# inputs.net
KiCad netlist of a schematic drawn in Altium Designer
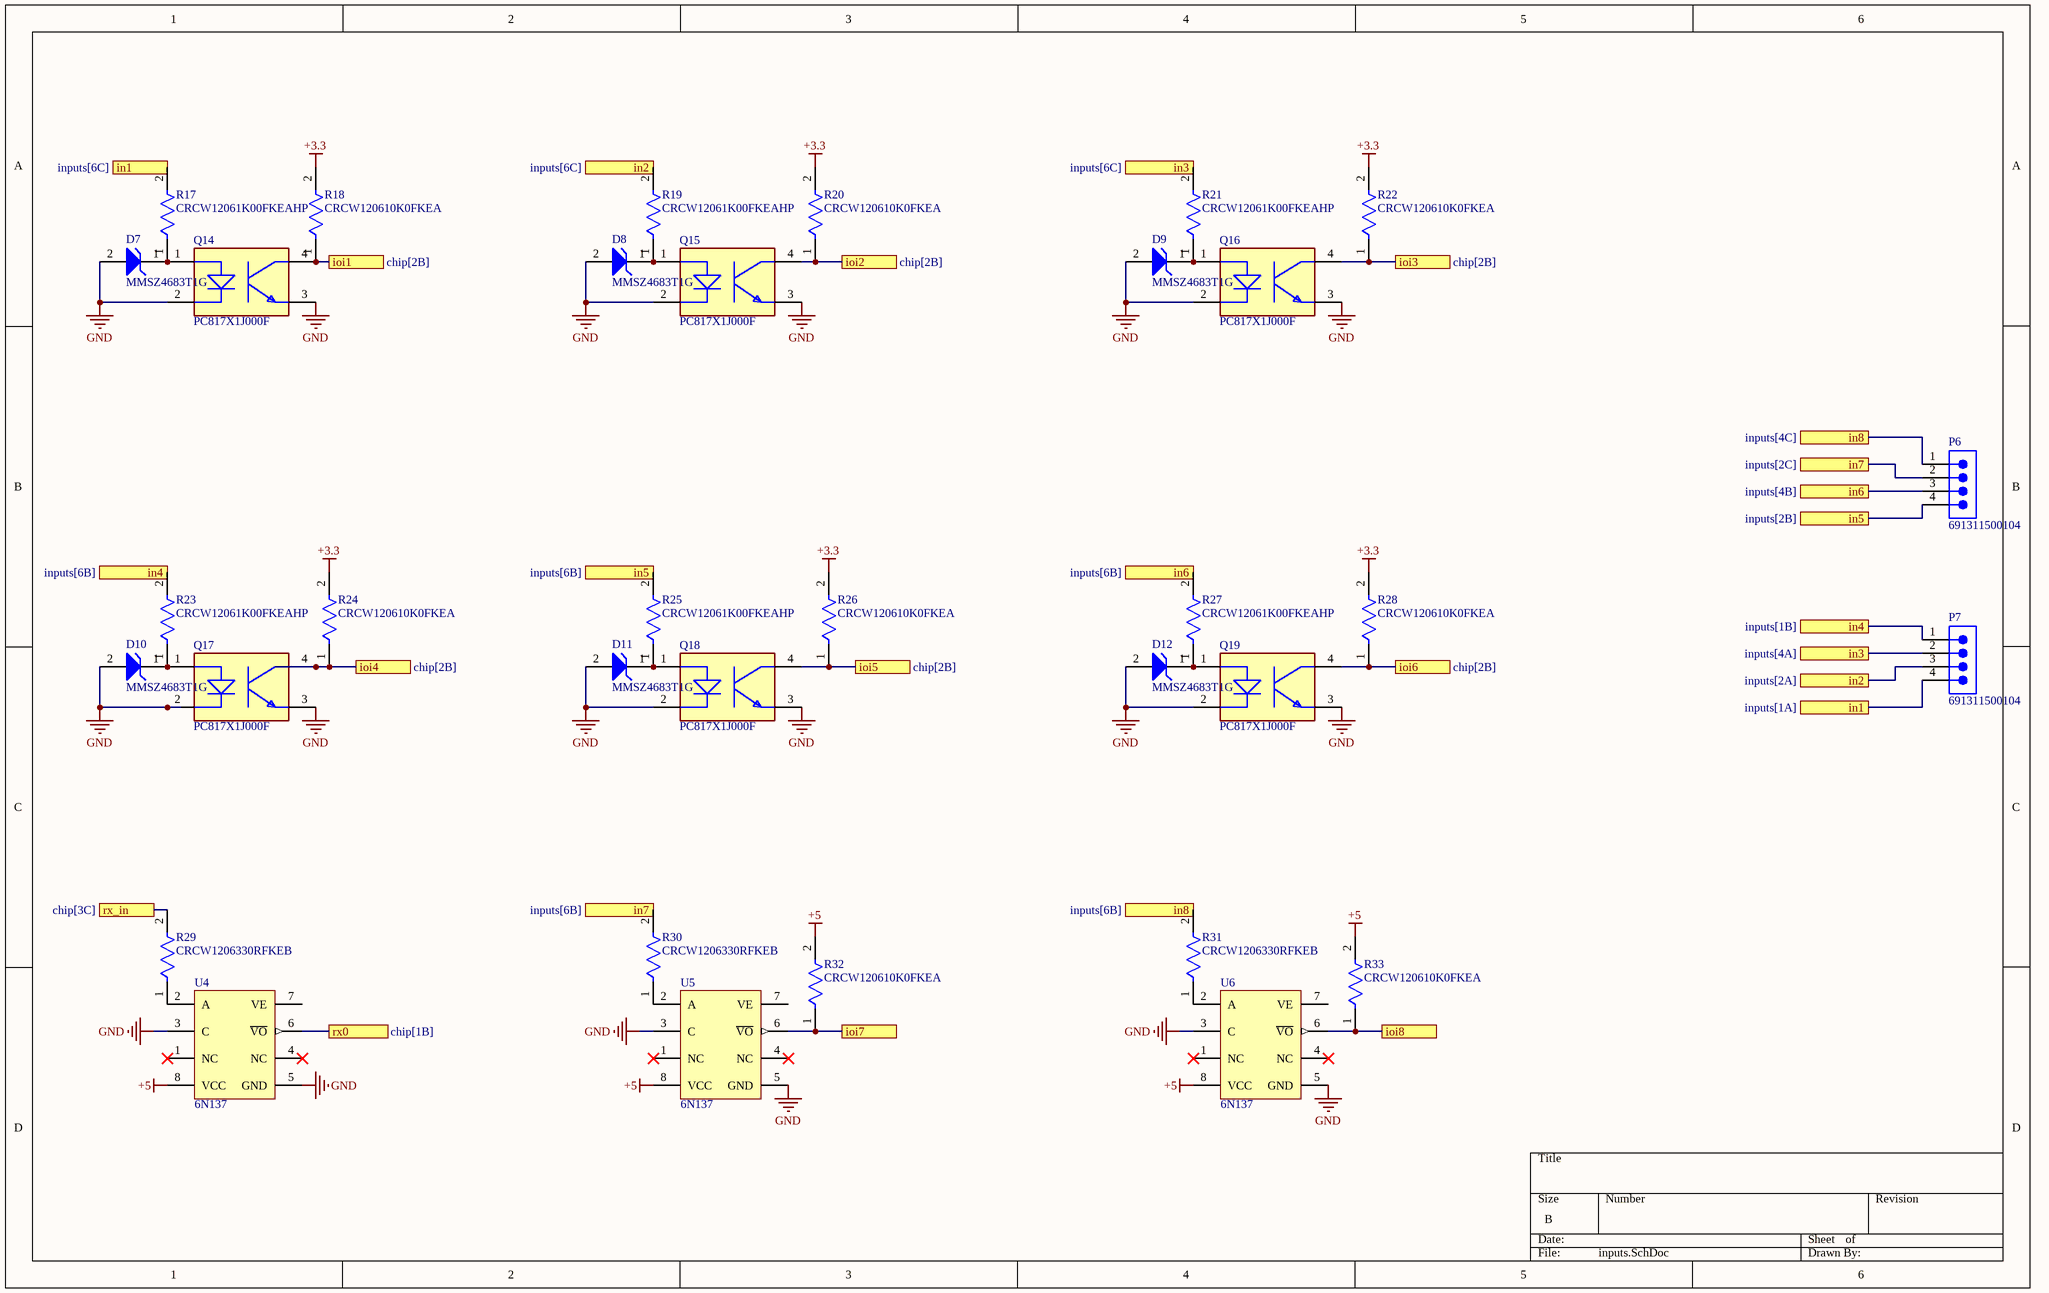
[diagram p0: inputs.SchDoc]

(export (version "E")
  (design (tool "Eeschema 10.0.6"))
  (components
    (comp (ref "D7")
      (value "MMSZ4683T1G")
      (footprint "ONSC-SOD-123-2-425-04_V")
      (description "Zener Voltage Regulator, 500 mW, 2-Pin SOD-123, Pb-Free, Tape and Reel")
      (fields (field (name "MANUFACTURER") "On Semiconductor"))
      (libsource (lib "Altium Content Vault") (part "ONSC-K1A2-2"))
    )
    (comp (ref "D8")
      (value "MMSZ4683T1G")
      (footprint "ONSC-SOD-123-2-425-04_V")
      (description "Zener Voltage Regulator, 500 mW, 2-Pin SOD-123, Pb-Free, Tape and Reel")
      (fields (field (name "MANUFACTURER") "On Semiconductor"))
      (libsource (lib "Altium Content Vault") (part "ONSC-K1A2-2"))
    )
    (comp (ref "D9")
      (value "MMSZ4683T1G")
      (footprint "ONSC-SOD-123-2-425-04_V")
      (description "Zener Voltage Regulator, 500 mW, 2-Pin SOD-123, Pb-Free, Tape and Reel")
      (fields (field (name "MANUFACTURER") "On Semiconductor"))
      (libsource (lib "Altium Content Vault") (part "ONSC-K1A2-2"))
    )
    (comp (ref "D10")
      (value "MMSZ4683T1G")
      (footprint "ONSC-SOD-123-2-425-04_V")
      (description "Zener Voltage Regulator, 500 mW, 2-Pin SOD-123, Pb-Free, Tape and Reel")
      (fields (field (name "MANUFACTURER") "On Semiconductor"))
      (libsource (lib "Altium Content Vault") (part "ONSC-K1A2-2"))
    )
    (comp (ref "D11")
      (value "MMSZ4683T1G")
      (footprint "ONSC-SOD-123-2-425-04_V")
      (description "Zener Voltage Regulator, 500 mW, 2-Pin SOD-123, Pb-Free, Tape and Reel")
      (fields (field (name "MANUFACTURER") "On Semiconductor"))
      (libsource (lib "Altium Content Vault") (part "ONSC-K1A2-2"))
    )
    (comp (ref "D12")
      (value "MMSZ4683T1G")
      (footprint "ONSC-SOD-123-2-425-04_V")
      (description "Zener Voltage Regulator, 500 mW, 2-Pin SOD-123, Pb-Free, Tape and Reel")
      (fields (field (name "MANUFACTURER") "On Semiconductor"))
      (libsource (lib "Altium Content Vault") (part "ONSC-K1A2-2"))
    )
    (comp (ref "P6")
      (value "691311500104")
      (footprint "691311500104")
      (fields (field (name "VOLTAGE") "300V"))
      (libsource (lib "Altium Content Vault") (part "TBL - 1R - 04P - Male"))
    )
    (comp (ref "P7")
      (value "691311500104")
      (footprint "691311500104")
      (fields (field (name "VOLTAGE") "300V"))
      (libsource (lib "Altium Content Vault") (part "TBL - 1R - 04P - Male"))
    )
    (comp (ref "Q14")
      (value "PC817X1J000F")
      (footprint "FP-PC817X1J000F-MFG")
      (description "OPTOISOLATOR 5KV TRANS 4DIP")
      (libsource (lib "Altium Content Vault") (part "8d9d817270a4e8f0d794346117f6aa3"))
    )
    (comp (ref "Q15")
      (value "PC817X1J000F")
      (footprint "FP-PC817X1J000F-MFG")
      (description "OPTOISOLATOR 5KV TRANS 4DIP")
      (libsource (lib "Altium Content Vault") (part "8d9d817270a4e8f0d794346117f6aa3"))
    )
    (comp (ref "Q16")
      (value "PC817X1J000F")
      (footprint "FP-PC817X1J000F-MFG")
      (description "OPTOISOLATOR 5KV TRANS 4DIP")
      (libsource (lib "Altium Content Vault") (part "8d9d817270a4e8f0d794346117f6aa3"))
    )
    (comp (ref "Q17")
      (value "PC817X1J000F")
      (footprint "FP-PC817X1J000F-MFG")
      (description "OPTOISOLATOR 5KV TRANS 4DIP")
      (libsource (lib "Altium Content Vault") (part "8d9d817270a4e8f0d794346117f6aa3"))
    )
    (comp (ref "Q18")
      (value "PC817X1J000F")
      (footprint "FP-PC817X1J000F-MFG")
      (description "OPTOISOLATOR 5KV TRANS 4DIP")
      (libsource (lib "Altium Content Vault") (part "8d9d817270a4e8f0d794346117f6aa3"))
    )
    (comp (ref "Q19")
      (value "PC817X1J000F")
      (footprint "FP-PC817X1J000F-MFG")
      (description "OPTOISOLATOR 5KV TRANS 4DIP")
      (libsource (lib "Altium Content Vault") (part "8d9d817270a4e8f0d794346117f6aa3"))
    )
    (comp (ref "R17")
      (value "CRCW12061K00FKEAHP")
      (footprint "FP-CRCW1206-HPe3-MFG")
      (description "RES SMD 1K OHM 1% 3/4W 1206")
      (fields
        (field (name "TOLERANCE") "1%")
        (field (name "OCTOPART") "https://octopart.com/crcw12061k00fkeahp-vishay-42635114")
      )
      (libsource (lib "Altium Content Vault") (part "1029c3af85768c4190bb7ad29bc67b5"))
    )
    (comp (ref "R18")
      (value "CRCW120610K0FKEA")
      (footprint "FP-CRCW1206-e3-IPC_C")
      (description "RES Thick Film, 10kΩ, 1%, 0.25W, 100ppm/°C, 1206")
      (fields (field (name "TOLERANCE") "1%"))
      (libsource (lib "Altium Content Vault") (part "1029c3af85768c4190bb7ad29bc67b5"))
    )
    (comp (ref "R19")
      (value "CRCW12061K00FKEAHP")
      (footprint "FP-CRCW1206-HPe3-MFG")
      (description "RES SMD 1K OHM 1% 3/4W 1206")
      (fields
        (field (name "TOLERANCE") "1%")
        (field (name "OCTOPART") "https://octopart.com/crcw12061k00fkeahp-vishay-42635114")
      )
      (libsource (lib "Altium Content Vault") (part "1029c3af85768c4190bb7ad29bc67b5"))
    )
    (comp (ref "R20")
      (value "CRCW120610K0FKEA")
      (footprint "FP-CRCW1206-e3-IPC_C")
      (description "RES Thick Film, 10kΩ, 1%, 0.25W, 100ppm/°C, 1206")
      (fields (field (name "TOLERANCE") "1%"))
      (libsource (lib "Altium Content Vault") (part "1029c3af85768c4190bb7ad29bc67b5"))
    )
    (comp (ref "R21")
      (value "CRCW12061K00FKEAHP")
      (footprint "FP-CRCW1206-HPe3-MFG")
      (description "RES SMD 1K OHM 1% 3/4W 1206")
      (fields
        (field (name "TOLERANCE") "1%")
        (field (name "OCTOPART") "https://octopart.com/crcw12061k00fkeahp-vishay-42635114")
      )
      (libsource (lib "Altium Content Vault") (part "1029c3af85768c4190bb7ad29bc67b5"))
    )
    (comp (ref "R22")
      (value "CRCW120610K0FKEA")
      (footprint "FP-CRCW1206-e3-IPC_C")
      (description "RES Thick Film, 10kΩ, 1%, 0.25W, 100ppm/°C, 1206")
      (fields (field (name "TOLERANCE") "1%"))
      (libsource (lib "Altium Content Vault") (part "1029c3af85768c4190bb7ad29bc67b5"))
    )
    (comp (ref "R23")
      (value "CRCW12061K00FKEAHP")
      (footprint "FP-CRCW1206-HPe3-MFG")
      (description "RES SMD 1K OHM 1% 3/4W 1206")
      (fields
        (field (name "TOLERANCE") "1%")
        (field (name "OCTOPART") "https://octopart.com/crcw12061k00fkeahp-vishay-42635114")
      )
      (libsource (lib "Altium Content Vault") (part "1029c3af85768c4190bb7ad29bc67b5"))
    )
    (comp (ref "R24")
      (value "CRCW120610K0FKEA")
      (footprint "FP-CRCW1206-e3-IPC_C")
      (description "RES Thick Film, 10kΩ, 1%, 0.25W, 100ppm/°C, 1206")
      (fields (field (name "TOLERANCE") "1%"))
      (libsource (lib "Altium Content Vault") (part "1029c3af85768c4190bb7ad29bc67b5"))
    )
    (comp (ref "R25")
      (value "CRCW12061K00FKEAHP")
      (footprint "FP-CRCW1206-HPe3-MFG")
      (description "RES SMD 1K OHM 1% 3/4W 1206")
      (fields
        (field (name "TOLERANCE") "1%")
        (field (name "OCTOPART") "https://octopart.com/crcw12061k00fkeahp-vishay-42635114")
      )
      (libsource (lib "Altium Content Vault") (part "1029c3af85768c4190bb7ad29bc67b5"))
    )
    (comp (ref "R26")
      (value "CRCW120610K0FKEA")
      (footprint "FP-CRCW1206-e3-IPC_C")
      (description "RES Thick Film, 10kΩ, 1%, 0.25W, 100ppm/°C, 1206")
      (fields (field (name "TOLERANCE") "1%"))
      (libsource (lib "Altium Content Vault") (part "1029c3af85768c4190bb7ad29bc67b5"))
    )
    (comp (ref "R27")
      (value "CRCW12061K00FKEAHP")
      (footprint "FP-CRCW1206-HPe3-MFG")
      (description "RES SMD 1K OHM 1% 3/4W 1206")
      (fields
        (field (name "TOLERANCE") "1%")
        (field (name "OCTOPART") "https://octopart.com/crcw12061k00fkeahp-vishay-42635114")
      )
      (libsource (lib "Altium Content Vault") (part "1029c3af85768c4190bb7ad29bc67b5"))
    )
    (comp (ref "R28")
      (value "CRCW120610K0FKEA")
      (footprint "FP-CRCW1206-e3-IPC_C")
      (description "RES Thick Film, 10kΩ, 1%, 0.25W, 100ppm/°C, 1206")
      (fields (field (name "TOLERANCE") "1%"))
      (libsource (lib "Altium Content Vault") (part "1029c3af85768c4190bb7ad29bc67b5"))
    )
    (comp (ref "R29")
      (value "CRCW1206330RFKEB")
      (footprint "FP-CRCW1206-e3-IPC_A")
      (description "RES Thick Film, 330Ω, 1%, 0.25W, 100ppm/°C, 1206")
      (fields (field (name "TOLERANCE") "1%"))
      (libsource (lib "Altium Content Vault") (part "1029c3af85768c4190bb7ad29bc67b5"))
    )
    (comp (ref "R30")
      (value "CRCW1206330RFKEB")
      (footprint "FP-CRCW1206-e3-IPC_A")
      (description "RES Thick Film, 330Ω, 1%, 0.25W, 100ppm/°C, 1206")
      (fields (field (name "TOLERANCE") "1%"))
      (libsource (lib "Altium Content Vault") (part "1029c3af85768c4190bb7ad29bc67b5"))
    )
    (comp (ref "R31")
      (value "CRCW1206330RFKEB")
      (footprint "FP-CRCW1206-e3-IPC_A")
      (description "RES Thick Film, 330Ω, 1%, 0.25W, 100ppm/°C, 1206")
      (fields (field (name "TOLERANCE") "1%"))
      (libsource (lib "Altium Content Vault") (part "1029c3af85768c4190bb7ad29bc67b5"))
    )
    (comp (ref "R32")
      (value "CRCW120610K0FKEA")
      (footprint "FP-CRCW1206-e3-IPC_C")
      (description "RES Thick Film, 10kΩ, 1%, 0.25W, 100ppm/°C, 1206")
      (fields (field (name "TOLERANCE") "1%"))
      (libsource (lib "Altium Content Vault") (part "1029c3af85768c4190bb7ad29bc67b5"))
    )
    (comp (ref "R33")
      (value "CRCW120610K0FKEA")
      (footprint "FP-CRCW1206-e3-IPC_C")
      (description "RES Thick Film, 10kΩ, 1%, 0.25W, 100ppm/°C, 1206")
      (fields (field (name "TOLERANCE") "1%"))
      (libsource (lib "Altium Content Vault") (part "1029c3af85768c4190bb7ad29bc67b5"))
    )
    (comp (ref "U4")
      (value "6N137")
      (footprint "VISH-DIP-8_A")
      (description "High Speed Optocoupler, Single and Dual, 10 MBd, 5 V, -40 to 100 degC, 8-Pin DIP, RoHS, Tube")
      (fields (field (name "MANUFACTURER") "Vishay"))
      (libsource (lib "Altium Content Vault") (part "VISH-6N137-DIP-8"))
    )
    (comp (ref "U5")
      (value "6N137")
      (footprint "VISH-DIP-8_A")
      (description "High Speed Optocoupler, Single and Dual, 10 MBd, 5 V, -40 to 100 degC, 8-Pin DIP, RoHS, Tube")
      (fields (field (name "MANUFACTURER") "Vishay"))
      (libsource (lib "Altium Content Vault") (part "VISH-6N137-DIP-8"))
    )
    (comp (ref "U6")
      (value "6N137")
      (footprint "VISH-DIP-8_A")
      (description "High Speed Optocoupler, Single and Dual, 10 MBd, 5 V, -40 to 100 degC, 8-Pin DIP, RoHS, Tube")
      (fields (field (name "MANUFACTURER") "Vishay"))
      (libsource (lib "Altium Content Vault") (part "VISH-6N137-DIP-8"))
    )
  )
  (nets
    (net (code "1") (name "+3.3") (class "Default")
      (node (ref "R18") (pin "2") (pinfunction "2_2") (pintype "passive"))
      (node (ref "R20") (pin "2") (pinfunction "2_2") (pintype "passive"))
      (node (ref "R22") (pin "2") (pinfunction "2_2") (pintype "passive"))
      (node (ref "R24") (pin "2") (pinfunction "2_2") (pintype "passive"))
      (node (ref "R26") (pin "2") (pinfunction "2_2") (pintype "passive"))
      (node (ref "R28") (pin "2") (pinfunction "2_2") (pintype "passive"))
    )
    (net (code "2") (name "+5") (class "Default")
      (node (ref "R32") (pin "2") (pinfunction "2_2") (pintype "passive"))
      (node (ref "R33") (pin "2") (pinfunction "2_2") (pintype "passive"))
      (node (ref "U4") (pin "8") (pinfunction "VCC_8") (pintype "power_in"))
      (node (ref "U5") (pin "8") (pinfunction "VCC_8") (pintype "power_in"))
      (node (ref "U6") (pin "8") (pinfunction "VCC_8") (pintype "power_in"))
    )
    (net (code "3") (name "/in1") (class "Default")
      (node (ref "P7") (pin "4") (pinfunction "4_4") (pintype "passive"))
      (node (ref "R17") (pin "2") (pinfunction "2_2") (pintype "passive"))
    )
    (net (code "4") (name "/in2") (class "Default")
      (node (ref "P7") (pin "3") (pinfunction "3_3") (pintype "passive"))
      (node (ref "R19") (pin "2") (pinfunction "2_2") (pintype "passive"))
    )
    (net (code "5") (name "/in3") (class "Default")
      (node (ref "P7") (pin "2") (pinfunction "2_2") (pintype "passive"))
      (node (ref "R21") (pin "2") (pinfunction "2_2") (pintype "passive"))
    )
    (net (code "6") (name "/in4") (class "Default")
      (node (ref "P7") (pin "1") (pinfunction "1_1") (pintype "passive"))
      (node (ref "R23") (pin "2") (pinfunction "2_2") (pintype "passive"))
    )
    (net (code "7") (name "/in5") (class "Default")
      (node (ref "P6") (pin "4") (pinfunction "4_4") (pintype "passive"))
      (node (ref "R25") (pin "2") (pinfunction "2_2") (pintype "passive"))
    )
    (net (code "8") (name "/in6") (class "Default")
      (node (ref "P6") (pin "3") (pinfunction "3_3") (pintype "passive"))
      (node (ref "R27") (pin "2") (pinfunction "2_2") (pintype "passive"))
    )
    (net (code "9") (name "/in7") (class "Default")
      (node (ref "P6") (pin "2") (pinfunction "2_2") (pintype "passive"))
      (node (ref "R30") (pin "2") (pinfunction "2_2") (pintype "passive"))
    )
    (net (code "10") (name "/in8") (class "Default")
      (node (ref "P6") (pin "1") (pinfunction "1_1") (pintype "passive"))
      (node (ref "R31") (pin "2") (pinfunction "2_2") (pintype "passive"))
    )
    (net (code "11") (name "/ioi1") (class "Default")
      (node (ref "Q14") (pin "4") (pinfunction "C_4") (pintype "passive"))
      (node (ref "R18") (pin "1") (pinfunction "1_1") (pintype "passive"))
    )
    (net (code "12") (name "/ioi2") (class "Default")
      (node (ref "Q15") (pin "4") (pinfunction "C_4") (pintype "passive"))
      (node (ref "R20") (pin "1") (pinfunction "1_1") (pintype "passive"))
    )
    (net (code "13") (name "/ioi3") (class "Default")
      (node (ref "Q16") (pin "4") (pinfunction "C_4") (pintype "passive"))
      (node (ref "R22") (pin "1") (pinfunction "1_1") (pintype "passive"))
    )
    (net (code "14") (name "/ioi4") (class "Default")
      (node (ref "Q17") (pin "4") (pinfunction "C_4") (pintype "passive"))
      (node (ref "R24") (pin "1") (pinfunction "1_1") (pintype "passive"))
    )
    (net (code "15") (name "/ioi5") (class "Default")
      (node (ref "Q18") (pin "4") (pinfunction "C_4") (pintype "passive"))
      (node (ref "R26") (pin "1") (pinfunction "1_1") (pintype "passive"))
    )
    (net (code "16") (name "/ioi6") (class "Default")
      (node (ref "Q19") (pin "4") (pinfunction "C_4") (pintype "passive"))
      (node (ref "R28") (pin "1") (pinfunction "1_1") (pintype "passive"))
    )
    (net (code "17") (name "/ioi7") (class "Default")
      (node (ref "R32") (pin "1") (pinfunction "1_1") (pintype "passive"))
      (node (ref "U5") (pin "6") (pinfunction "~{VO}_6") (pintype "output"))
    )
    (net (code "18") (name "/ioi8") (class "Default")
      (node (ref "R33") (pin "1") (pinfunction "1_1") (pintype "passive"))
      (node (ref "U6") (pin "6") (pinfunction "~{VO}_6") (pintype "output"))
    )
    (net (code "19") (name "/rx0") (class "Default")
      (node (ref "U4") (pin "6") (pinfunction "~{VO}_6") (pintype "output"))
    )
    (net (code "20") (name "/rx_in") (class "Default")
      (node (ref "R29") (pin "2") (pinfunction "2_2") (pintype "passive"))
    )
    (net (code "21") (name "GND") (class "Default")
      (node (ref "D10") (pin "2") (pinfunction "A_2") (pintype "passive"))
      (node (ref "D11") (pin "2") (pinfunction "A_2") (pintype "passive"))
      (node (ref "D12") (pin "2") (pinfunction "A_2") (pintype "passive"))
      (node (ref "D7") (pin "2") (pinfunction "A_2") (pintype "passive"))
      (node (ref "D8") (pin "2") (pinfunction "A_2") (pintype "passive"))
      (node (ref "D9") (pin "2") (pinfunction "A_2") (pintype "passive"))
      (node (ref "Q14") (pin "2") (pinfunction "C_2") (pintype "passive"))
      (node (ref "Q14") (pin "3") (pinfunction "E_3") (pintype "passive"))
      (node (ref "Q15") (pin "2") (pinfunction "C_2") (pintype "passive"))
      (node (ref "Q15") (pin "3") (pinfunction "E_3") (pintype "passive"))
      (node (ref "Q16") (pin "2") (pinfunction "C_2") (pintype "passive"))
      (node (ref "Q16") (pin "3") (pinfunction "E_3") (pintype "passive"))
      (node (ref "Q17") (pin "2") (pinfunction "C_2") (pintype "passive"))
      (node (ref "Q17") (pin "3") (pinfunction "E_3") (pintype "passive"))
      (node (ref "Q18") (pin "2") (pinfunction "C_2") (pintype "passive"))
      (node (ref "Q18") (pin "3") (pinfunction "E_3") (pintype "passive"))
      (node (ref "Q19") (pin "2") (pinfunction "C_2") (pintype "passive"))
      (node (ref "Q19") (pin "3") (pinfunction "E_3") (pintype "passive"))
      (node (ref "U4") (pin "3") (pinfunction "C_3") (pintype "passive"))
      (node (ref "U4") (pin "5") (pinfunction "GND_5") (pintype "power_in"))
      (node (ref "U5") (pin "3") (pinfunction "C_3") (pintype "passive"))
      (node (ref "U5") (pin "5") (pinfunction "GND_5") (pintype "power_in"))
      (node (ref "U6") (pin "3") (pinfunction "C_3") (pintype "passive"))
      (node (ref "U6") (pin "5") (pinfunction "GND_5") (pintype "power_in"))
    )
    (net (code "22") (name "Net-(D7-K)") (class "Default")
      (node (ref "D7") (pin "1") (pinfunction "K_1") (pintype "passive"))
      (node (ref "Q14") (pin "1") (pinfunction "A_1") (pintype "passive"))
      (node (ref "R17") (pin "1") (pinfunction "1_1") (pintype "passive"))
    )
    (net (code "23") (name "Net-(D8-K)") (class "Default")
      (node (ref "D8") (pin "1") (pinfunction "K_1") (pintype "passive"))
      (node (ref "Q15") (pin "1") (pinfunction "A_1") (pintype "passive"))
      (node (ref "R19") (pin "1") (pinfunction "1_1") (pintype "passive"))
    )
    (net (code "24") (name "Net-(D9-K)") (class "Default")
      (node (ref "D9") (pin "1") (pinfunction "K_1") (pintype "passive"))
      (node (ref "Q16") (pin "1") (pinfunction "A_1") (pintype "passive"))
      (node (ref "R21") (pin "1") (pinfunction "1_1") (pintype "passive"))
    )
    (net (code "25") (name "Net-(D10-K)") (class "Default")
      (node (ref "D10") (pin "1") (pinfunction "K_1") (pintype "passive"))
      (node (ref "Q17") (pin "1") (pinfunction "A_1") (pintype "passive"))
      (node (ref "R23") (pin "1") (pinfunction "1_1") (pintype "passive"))
    )
    (net (code "26") (name "Net-(D11-K)") (class "Default")
      (node (ref "D11") (pin "1") (pinfunction "K_1") (pintype "passive"))
      (node (ref "Q18") (pin "1") (pinfunction "A_1") (pintype "passive"))
      (node (ref "R25") (pin "1") (pinfunction "1_1") (pintype "passive"))
    )
    (net (code "27") (name "Net-(D12-K)") (class "Default")
      (node (ref "D12") (pin "1") (pinfunction "K_1") (pintype "passive"))
      (node (ref "Q19") (pin "1") (pinfunction "A_1") (pintype "passive"))
      (node (ref "R27") (pin "1") (pinfunction "1_1") (pintype "passive"))
    )
    (net (code "28") (name "Net-(U4-A)") (class "Default")
      (node (ref "R29") (pin "1") (pinfunction "1_1") (pintype "passive"))
      (node (ref "U4") (pin "2") (pinfunction "A_2") (pintype "passive"))
    )
    (net (code "29") (name "Net-(U5-A)") (class "Default")
      (node (ref "R30") (pin "1") (pinfunction "1_1") (pintype "passive"))
      (node (ref "U5") (pin "2") (pinfunction "A_2") (pintype "passive"))
    )
    (net (code "30") (name "Net-(U6-A)") (class "Default")
      (node (ref "R31") (pin "1") (pinfunction "1_1") (pintype "passive"))
      (node (ref "U6") (pin "2") (pinfunction "A_2") (pintype "passive"))
    )
    (net (code "31") (name "unconnected-(U4-NC-Pad1)") (class "Default")
      (node (ref "U4") (pin "1") (pinfunction "NC_1") (pintype "passive+no_connect"))
    )
    (net (code "32") (name "unconnected-(U4-NC-Pad4)") (class "Default")
      (node (ref "U4") (pin "4") (pinfunction "NC_4") (pintype "passive+no_connect"))
    )
    (net (code "33") (name "unconnected-(U4-VE-Pad7)") (class "Default")
      (node (ref "U4") (pin "7") (pinfunction "VE_7") (pintype "power_in"))
    )
    (net (code "34") (name "unconnected-(U5-NC-Pad1)") (class "Default")
      (node (ref "U5") (pin "1") (pinfunction "NC_1") (pintype "passive+no_connect"))
    )
    (net (code "35") (name "unconnected-(U5-NC-Pad4)") (class "Default")
      (node (ref "U5") (pin "4") (pinfunction "NC_4") (pintype "passive+no_connect"))
    )
    (net (code "36") (name "unconnected-(U5-VE-Pad7)") (class "Default")
      (node (ref "U5") (pin "7") (pinfunction "VE_7") (pintype "power_in"))
    )
    (net (code "37") (name "unconnected-(U6-NC-Pad1)") (class "Default")
      (node (ref "U6") (pin "1") (pinfunction "NC_1") (pintype "passive+no_connect"))
    )
    (net (code "38") (name "unconnected-(U6-NC-Pad4)") (class "Default")
      (node (ref "U6") (pin "4") (pinfunction "NC_4") (pintype "passive+no_connect"))
    )
    (net (code "39") (name "unconnected-(U6-VE-Pad7)") (class "Default")
      (node (ref "U6") (pin "7") (pinfunction "VE_7") (pintype "power_in"))
    )
  )
)
